# rint.net
KiCad netlist of a schematic drawn in EAGLE
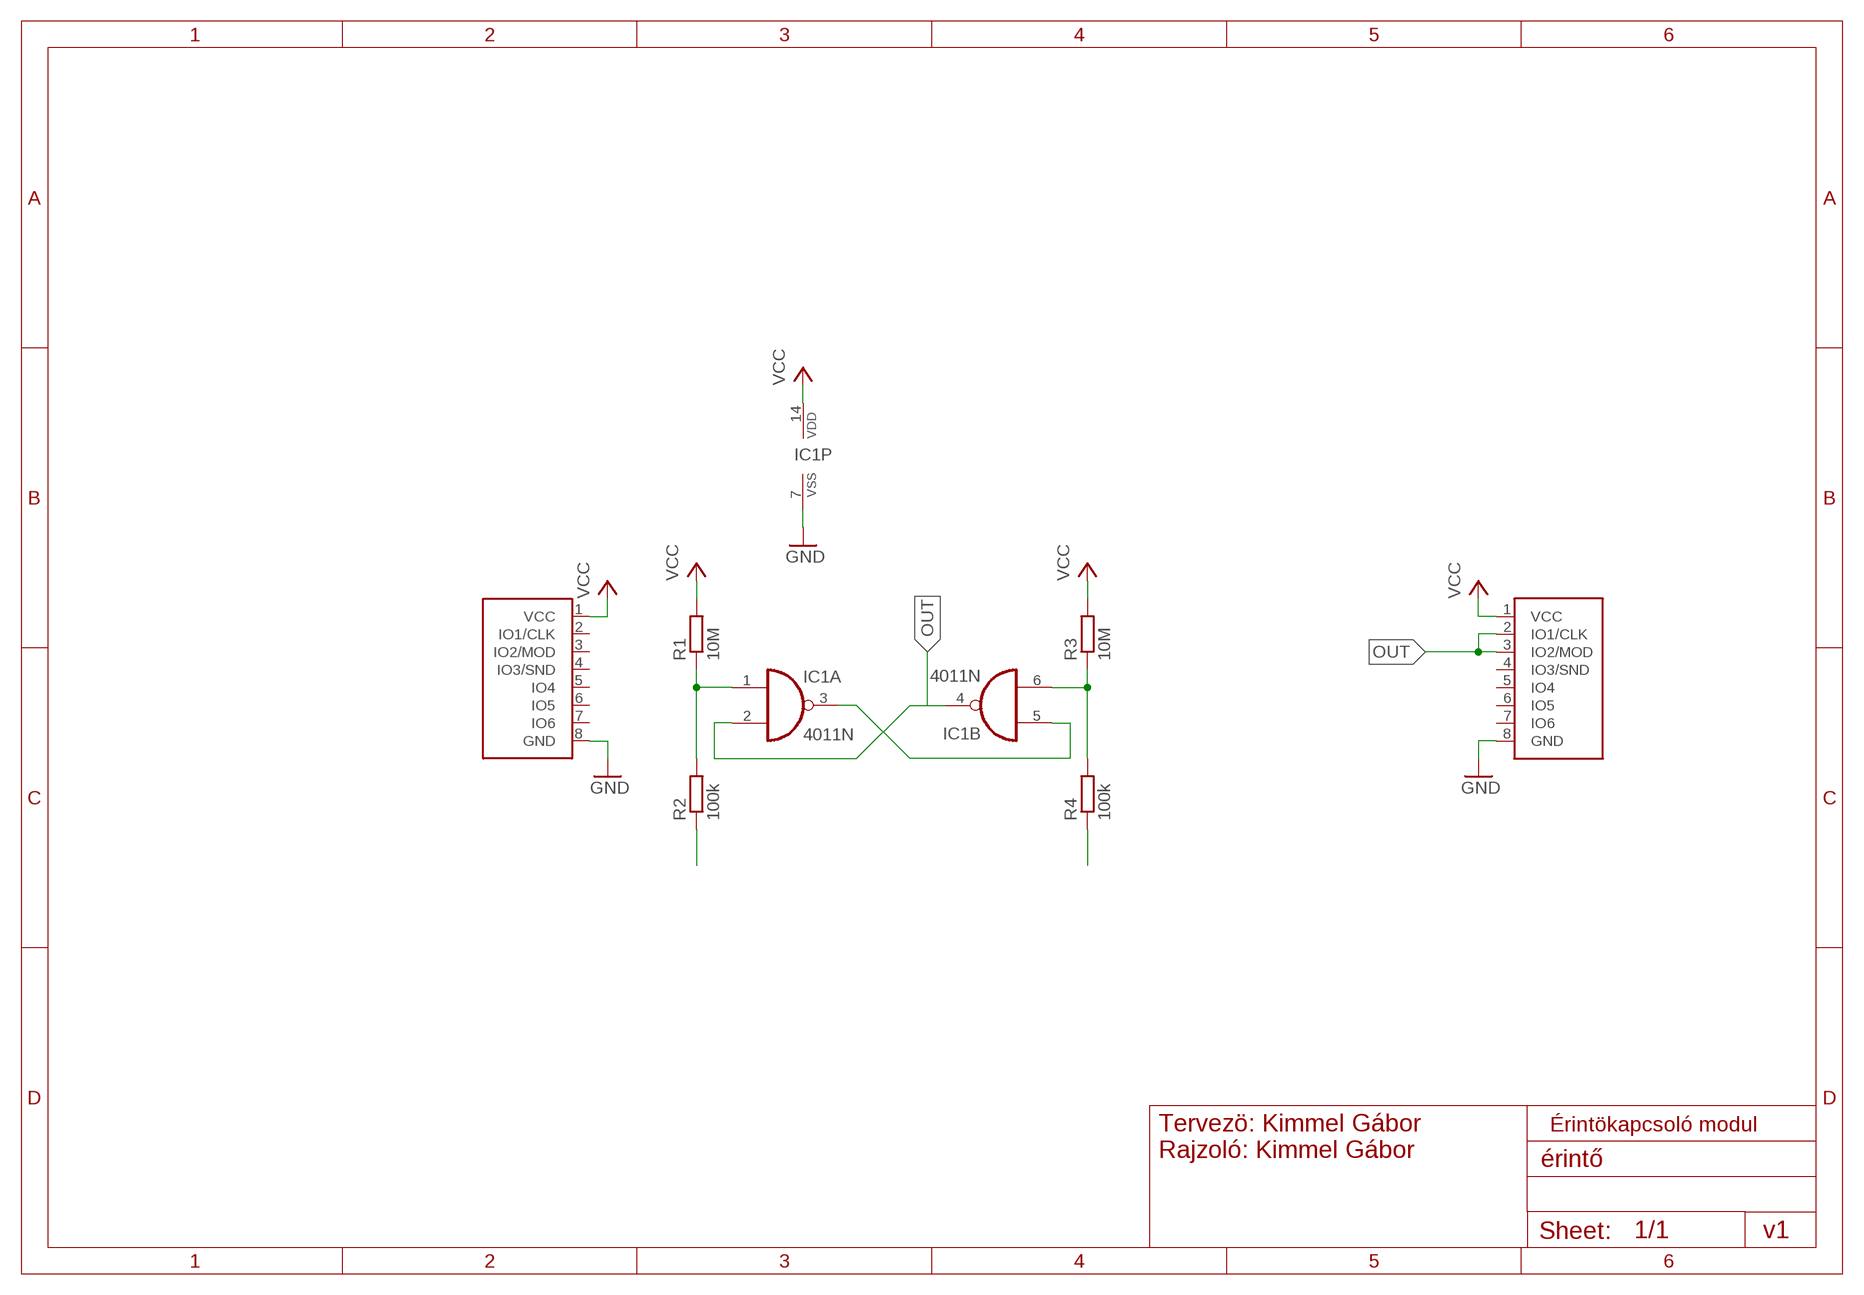
[diagram p0: schematic, sheet 1]

(export (version "E")
  (design (tool "Eeschema 10.0.6"))
  (components
    (comp (ref "IC1")
      (value "4011N")
      (footprint "eagle-import:DIL14")
      (libsource (lib "eagle-import") (part "4011N"))
    )
    (comp (ref "R1")
      (value "10M")
      (footprint "eagle-import:0309_12")
      (libsource (lib "eagle-import") (part "R-EU_0309/12"))
    )
    (comp (ref "R2")
      (value "100k")
      (footprint "eagle-import:0309_12")
      (libsource (lib "eagle-import") (part "R-EU_0309/12"))
    )
    (comp (ref "R3")
      (value "10M")
      (footprint "eagle-import:0309_12")
      (libsource (lib "eagle-import") (part "R-EU_0309/12"))
    )
    (comp (ref "R4")
      (value "100k")
      (footprint "eagle-import:0309_12")
      (libsource (lib "eagle-import") (part "R-EU_0309/12"))
    )
    (comp (ref "U$1")
      (value "GANZ-CONNECTOR")
      (footprint "eagle-import:FE08W")
      (libsource (lib "eagle-import") (part "GANZ-CONNECTOR"))
    )
    (comp (ref "U$2")
      (value "GANZ-CONNECTOR-OUT")
      (footprint "eagle-import:MA08-1W")
      (libsource (lib "eagle-import") (part "GANZ-CONNECTOR-OUT"))
    )
  )
  (nets
    (net (code "1") (name "GND") (class "Default")
      (node (ref "IC1") (pin "7") (pinfunction "VSS_7") (pintype "power_in"))
      (node (ref "U$1") (pin "8") (pinfunction "GND_8") (pintype "bidirectional"))
      (node (ref "U$2") (pin "8") (pinfunction "GND_8") (pintype "bidirectional"))
    )
    (net (code "2") (name "Net-(IC1A-I0)") (class "Default")
      (node (ref "IC1") (pin "1") (pinfunction "I0_1") (pintype "input"))
      (node (ref "R1") (pin "1") (pinfunction "1_1") (pintype "passive"))
      (node (ref "R2") (pin "2") (pinfunction "2_2") (pintype "passive"))
    )
    (net (code "3") (name "Net-(IC1A-O)") (class "Default")
      (node (ref "IC1") (pin "3") (pinfunction "O_3") (pintype "output"))
      (node (ref "IC1") (pin "5") (pinfunction "I0_5") (pintype "input"))
    )
    (net (code "4") (name "Net-(IC1B-I1)") (class "Default")
      (node (ref "IC1") (pin "6") (pinfunction "I1_6") (pintype "input"))
      (node (ref "R3") (pin "1") (pinfunction "1_1") (pintype "passive"))
      (node (ref "R4") (pin "2") (pinfunction "2_2") (pintype "passive"))
    )
    (net (code "5") (name "OUT") (class "Default")
      (node (ref "IC1") (pin "2") (pinfunction "I1_2") (pintype "input"))
      (node (ref "IC1") (pin "4") (pinfunction "O_4") (pintype "output"))
      (node (ref "U$2") (pin "2") (pinfunction "IO1/CLK_2") (pintype "bidirectional"))
      (node (ref "U$2") (pin "3") (pinfunction "IO2/MOD_3") (pintype "bidirectional"))
    )
    (net (code "6") (name "VCC") (class "Default")
      (node (ref "IC1") (pin "14") (pinfunction "VDD_14") (pintype "power_in"))
      (node (ref "R1") (pin "2") (pinfunction "2_2") (pintype "passive"))
      (node (ref "R3") (pin "2") (pinfunction "2_2") (pintype "passive"))
      (node (ref "U$1") (pin "1") (pinfunction "VCC_1") (pintype "bidirectional"))
      (node (ref "U$2") (pin "1") (pinfunction "VCC_1") (pintype "bidirectional"))
    )
    (net (code "7") (name "unconnected-(R2-Pad1)") (class "Default")
      (node (ref "R2") (pin "1") (pinfunction "1_1") (pintype "passive"))
    )
    (net (code "8") (name "unconnected-(R4-Pad1)") (class "Default")
      (node (ref "R4") (pin "1") (pinfunction "1_1") (pintype "passive"))
    )
    (net (code "9") (name "unconnected-(U$1-IO1{slash}CLK-Pad2)") (class "Default")
      (node (ref "U$1") (pin "2") (pinfunction "IO1/CLK_2") (pintype "bidirectional"))
    )
    (net (code "10") (name "unconnected-(U$1-IO2{slash}MOD-Pad3)") (class "Default")
      (node (ref "U$1") (pin "3") (pinfunction "IO2/MOD_3") (pintype "bidirectional"))
    )
    (net (code "11") (name "unconnected-(U$1-IO3{slash}SND-Pad4)") (class "Default")
      (node (ref "U$1") (pin "4") (pinfunction "IO3/SND_4") (pintype "bidirectional"))
    )
    (net (code "12") (name "unconnected-(U$1-IO4-Pad5)") (class "Default")
      (node (ref "U$1") (pin "5") (pinfunction "IO4_5") (pintype "bidirectional"))
    )
    (net (code "13") (name "unconnected-(U$1-IO5-Pad6)") (class "Default")
      (node (ref "U$1") (pin "6") (pinfunction "IO5_6") (pintype "bidirectional"))
    )
    (net (code "14") (name "unconnected-(U$1-IO6-Pad7)") (class "Default")
      (node (ref "U$1") (pin "7") (pinfunction "IO6_7") (pintype "bidirectional"))
    )
    (net (code "15") (name "unconnected-(U$2-IO3{slash}SND-Pad4)") (class "Default")
      (node (ref "U$2") (pin "4") (pinfunction "IO3/SND_4") (pintype "bidirectional"))
    )
    (net (code "16") (name "unconnected-(U$2-IO4-Pad5)") (class "Default")
      (node (ref "U$2") (pin "5") (pinfunction "IO4_5") (pintype "bidirectional"))
    )
    (net (code "17") (name "unconnected-(U$2-IO5-Pad6)") (class "Default")
      (node (ref "U$2") (pin "6") (pinfunction "IO5_6") (pintype "bidirectional"))
    )
    (net (code "18") (name "unconnected-(U$2-IO6-Pad7)") (class "Default")
      (node (ref "U$2") (pin "7") (pinfunction "IO6_7") (pintype "bidirectional"))
    )
  )
)
